# pcb-main.net
KiCad netlist of a schematic drawn in EAGLE
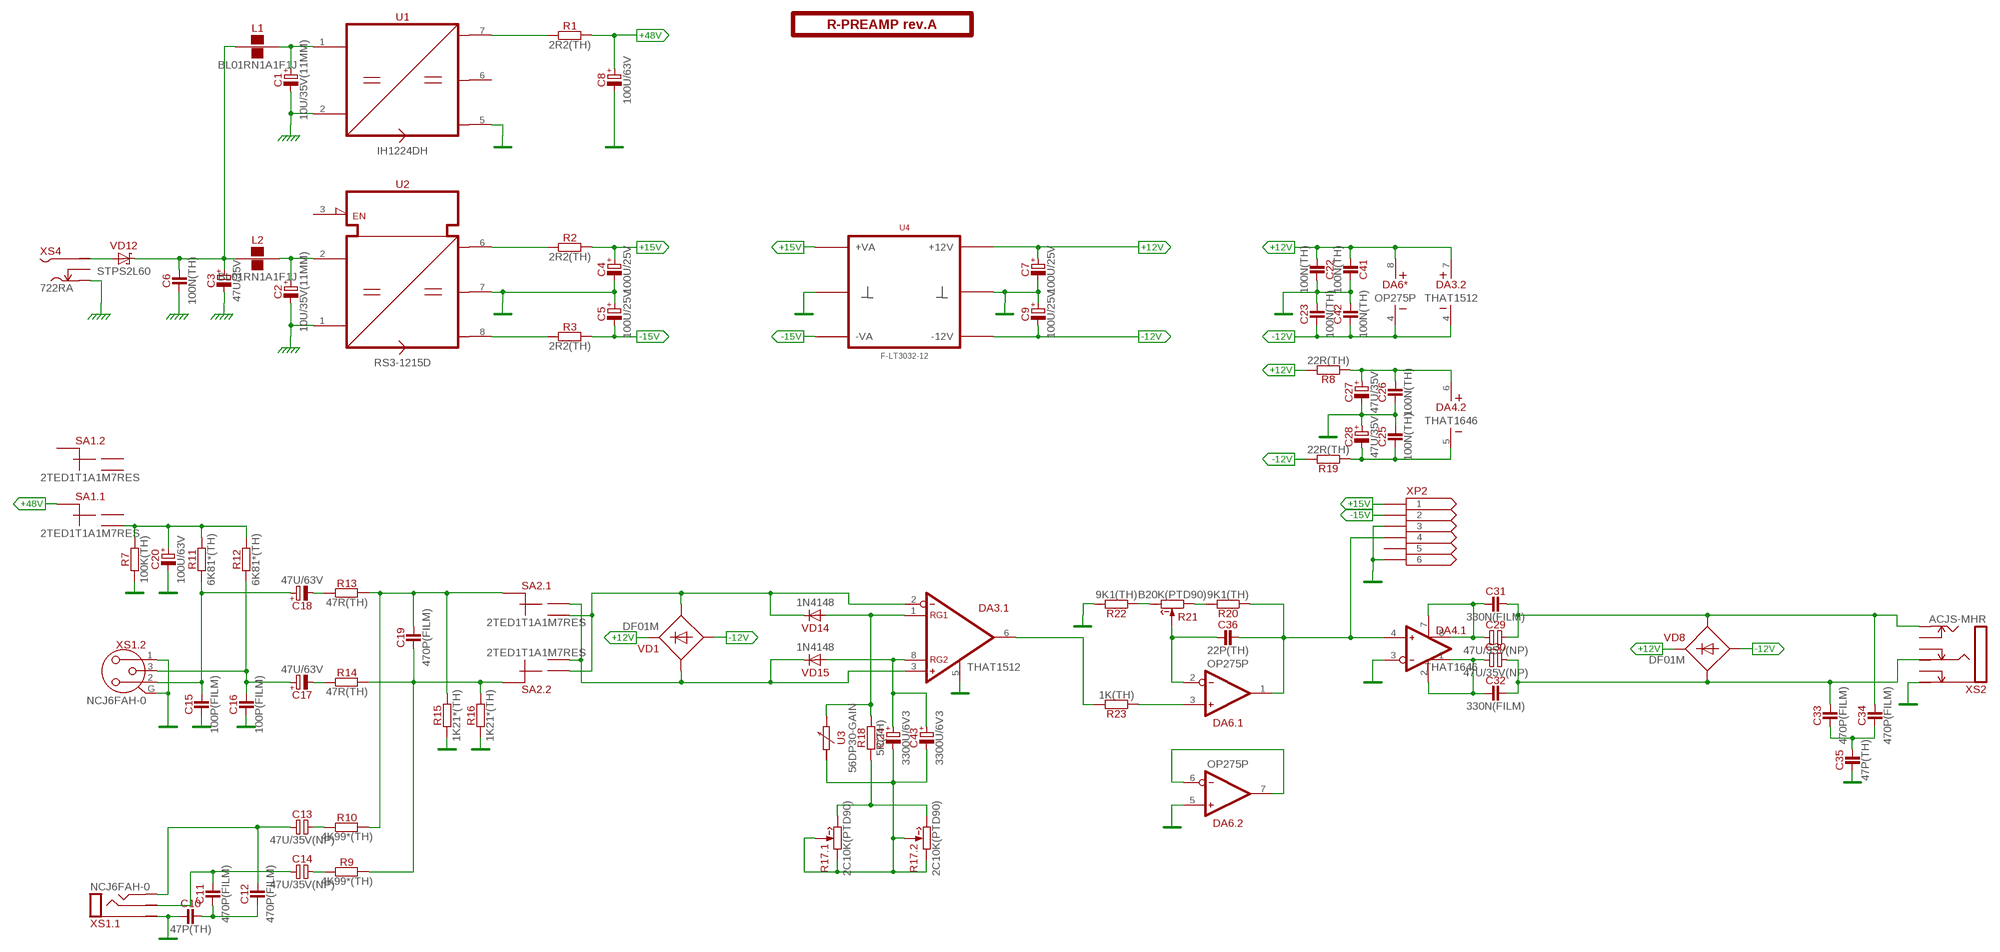
[diagram p0: schematic, sheet 1]

(export (version "E")
  (design (tool "Eeschema 10.0.6"))
  (components
    (comp (ref "C1")
      (value "10U/35V(11MM)")
      (footprint "eagle-import:E2-5")
      (libsource (lib "eagle-import") (part "?10U/35V(11MM)"))
    )
    (comp (ref "C2")
      (value "10U/35V(11MM)")
      (footprint "eagle-import:E2-5")
      (libsource (lib "eagle-import") (part "?10U/35V(11MM)"))
    )
    (comp (ref "C3")
      (value "47U/35V")
      (footprint "eagle-import:E2-5")
      (libsource (lib "eagle-import") (part "?47U/35V"))
    )
    (comp (ref "C4")
      (value "100U/25V")
      (footprint "eagle-import:E2,5-7")
      (libsource (lib "eagle-import") (part "?100U/25V"))
    )
    (comp (ref "C5")
      (value "100U/25V")
      (footprint "eagle-import:E2,5-7")
      (libsource (lib "eagle-import") (part "?100U/25V"))
    )
    (comp (ref "C6")
      (value "100N(TH)")
      (footprint "eagle-import:C050-024X044")
      (libsource (lib "eagle-import") (part "?100N(TH)"))
    )
    (comp (ref "C7")
      (value "100U/25V")
      (footprint "eagle-import:E2,5-7")
      (libsource (lib "eagle-import") (part "?100U/25V"))
    )
    (comp (ref "C8")
      (value "100U/63V")
      (footprint "eagle-import:E5-10,5")
      (libsource (lib "eagle-import") (part "?100U/63V"))
    )
    (comp (ref "C9")
      (value "100U/25V")
      (footprint "eagle-import:E2,5-7")
      (libsource (lib "eagle-import") (part "?100U/25V"))
    )
    (comp (ref "C10")
      (value "47P(TH)")
      (footprint "eagle-import:C050-024X044")
      (libsource (lib "eagle-import") (part "?47P(TH)"))
    )
    (comp (ref "C11")
      (value "470P(FILM)")
      (footprint "eagle-import:C050-055X075")
      (libsource (lib "eagle-import") (part "?470P(FILM)"))
    )
    (comp (ref "C12")
      (value "470P(FILM)")
      (footprint "eagle-import:C050-055X075")
      (libsource (lib "eagle-import") (part "?470P(FILM)"))
    )
    (comp (ref "C13")
      (value "47U/35V(NP)")
      (footprint "eagle-import:E5-10,5")
      (libsource (lib "eagle-import") (part "?(NP)47U/35V"))
    )
    (comp (ref "C14")
      (value "47U/35V(NP)")
      (footprint "eagle-import:E5-10,5")
      (libsource (lib "eagle-import") (part "?(NP)47U/35V"))
    )
    (comp (ref "C15")
      (value "100P(FILM)")
      (footprint "eagle-import:C050-045X075")
      (libsource (lib "eagle-import") (part "?100P(FILM)"))
    )
    (comp (ref "C16")
      (value "100P(FILM)")
      (footprint "eagle-import:C050-045X075")
      (libsource (lib "eagle-import") (part "?100P(FILM)"))
    )
    (comp (ref "C17")
      (value "47U/63V")
      (footprint "eagle-import:E5-10,5")
      (libsource (lib "eagle-import") (part "?47U/63V"))
    )
    (comp (ref "C18")
      (value "47U/63V")
      (footprint "eagle-import:E5-10,5")
      (libsource (lib "eagle-import") (part "?47U/63V"))
    )
    (comp (ref "C19")
      (value "470P(FILM)")
      (footprint "eagle-import:C050-055X075")
      (libsource (lib "eagle-import") (part "?470P(FILM)"))
    )
    (comp (ref "C20")
      (value "100U/63V")
      (footprint "eagle-import:E5-10,5")
      (libsource (lib "eagle-import") (part "?100U/63V"))
    )
    (comp (ref "C22")
      (value "100N(TH)")
      (footprint "eagle-import:C050-024X044")
      (libsource (lib "eagle-import") (part "?100N(TH)"))
    )
    (comp (ref "C23")
      (value "100N(TH)")
      (footprint "eagle-import:C050-024X044")
      (libsource (lib "eagle-import") (part "?100N(TH)"))
    )
    (comp (ref "C24")
      (value "3300U/6V3")
      (footprint "eagle-import:E5-10,5")
      (libsource (lib "eagle-import") (part "?3300U/6V3"))
    )
    (comp (ref "C25")
      (value "100N(TH)")
      (footprint "eagle-import:C050-024X044")
      (libsource (lib "eagle-import") (part "?100N(TH)"))
    )
    (comp (ref "C26")
      (value "100N(TH)")
      (footprint "eagle-import:C050-024X044")
      (libsource (lib "eagle-import") (part "?100N(TH)"))
    )
    (comp (ref "C27")
      (value "47U/35V")
      (footprint "eagle-import:E2-5")
      (libsource (lib "eagle-import") (part "?47U/35V"))
    )
    (comp (ref "C28")
      (value "47U/35V")
      (footprint "eagle-import:E2-5")
      (libsource (lib "eagle-import") (part "?47U/35V"))
    )
    (comp (ref "C29")
      (value "47U/35V(NP)")
      (footprint "eagle-import:E5-10,5")
      (libsource (lib "eagle-import") (part "?(NP)47U/35V"))
    )
    (comp (ref "C30")
      (value "47U/35V(NP)")
      (footprint "eagle-import:E5-10,5")
      (libsource (lib "eagle-import") (part "?(NP)47U/35V"))
    )
    (comp (ref "C31")
      (value "330N(FILM)")
      (footprint "eagle-import:C050-035X075")
      (libsource (lib "eagle-import") (part "?330N(FILM)"))
    )
    (comp (ref "C32")
      (value "330N(FILM)")
      (footprint "eagle-import:C050-035X075")
      (libsource (lib "eagle-import") (part "?330N(FILM)"))
    )
    (comp (ref "C33")
      (value "470P(FILM)")
      (footprint "eagle-import:C050-055X075")
      (libsource (lib "eagle-import") (part "?470P(FILM)"))
    )
    (comp (ref "C34")
      (value "470P(FILM)")
      (footprint "eagle-import:C050-055X075")
      (libsource (lib "eagle-import") (part "?470P(FILM)"))
    )
    (comp (ref "C35")
      (value "47P(TH)")
      (footprint "eagle-import:C050-024X044")
      (libsource (lib "eagle-import") (part "?47P(TH)"))
    )
    (comp (ref "C36")
      (value "22P(TH)")
      (footprint "eagle-import:C050-024X044")
      (libsource (lib "eagle-import") (part "?22P(TH)"))
    )
    (comp (ref "C41")
      (value "100N(TH)")
      (footprint "eagle-import:C050-024X044")
      (libsource (lib "eagle-import") (part "?100N(TH)"))
    )
    (comp (ref "C42")
      (value "100N(TH)")
      (footprint "eagle-import:C050-024X044")
      (libsource (lib "eagle-import") (part "?100N(TH)"))
    )
    (comp (ref "C43")
      (value "3300U/6V3")
      (footprint "eagle-import:E5-10,5")
      (libsource (lib "eagle-import") (part "?3300U/6V3"))
    )
    (comp (ref "DA3")
      (value "THAT1512")
      (footprint "eagle-import:DIP-8")
      (libsource (lib "eagle-import") (part "THAT1512"))
    )
    (comp (ref "DA4")
      (value "THAT1646")
      (footprint "eagle-import:DIP-8")
      (libsource (lib "eagle-import") (part "THAT1646"))
    )
    (comp (ref "DA6")
      (value "OP275P")
      (footprint "eagle-import:DIP-8")
      (libsource (lib "eagle-import") (part "OP275P"))
    )
    (comp (ref "L1")
      (value "BL01RN1A1F1J")
      (footprint "eagle-import:BL01RN1A")
      (libsource (lib "eagle-import") (part "BL01RN1A?1F1J"))
    )
    (comp (ref "L2")
      (value "BL01RN1A1F1J")
      (footprint "eagle-import:BL01RN1A")
      (libsource (lib "eagle-import") (part "BL01RN1A?1F1J"))
    )
    (comp (ref "PCB1")
      (value "R-PREAMP rev.A")
      (footprint "eagle-import:F-LOGO")
      (libsource (lib "eagle-import") (part "GENERIC-LOGO"))
    )
    (comp (ref "R1")
      (value "2R2(TH)")
      (footprint "eagle-import:R-0207_10")
      (libsource (lib "eagle-import") (part "?2R2(TH)"))
    )
    (comp (ref "R2")
      (value "2R2(TH)")
      (footprint "eagle-import:R-0207_10")
      (libsource (lib "eagle-import") (part "?2R2(TH)"))
    )
    (comp (ref "R3")
      (value "2R2(TH)")
      (footprint "eagle-import:R-0207_10")
      (libsource (lib "eagle-import") (part "?2R2(TH)"))
    )
    (comp (ref "R7")
      (value "100K(TH)")
      (footprint "eagle-import:R-0207_10")
      (libsource (lib "eagle-import") (part "resistors_?100K(TH)"))
    )
    (comp (ref "R8")
      (value "22R(TH)")
      (footprint "eagle-import:R-0207_10")
      (libsource (lib "eagle-import") (part "?22R(TH)"))
    )
    (comp (ref "R9")
      (value "4K99*(TH)")
      (footprint "eagle-import:R-0207_10")
      (libsource (lib "eagle-import") (part "?4K99(TH)"))
    )
    (comp (ref "R10")
      (value "4K99*(TH)")
      (footprint "eagle-import:R-0207_10")
      (libsource (lib "eagle-import") (part "?4K99(TH)"))
    )
    (comp (ref "R11")
      (value "6K81*(TH)")
      (footprint "eagle-import:R-0207_10")
      (libsource (lib "eagle-import") (part "?6K81(TH)"))
    )
    (comp (ref "R12")
      (value "6K81*(TH)")
      (footprint "eagle-import:R-0207_10")
      (libsource (lib "eagle-import") (part "?6K81(TH)"))
    )
    (comp (ref "R13")
      (value "47R(TH)")
      (footprint "eagle-import:R-0207_10")
      (libsource (lib "eagle-import") (part "?47R(TH)"))
    )
    (comp (ref "R14")
      (value "47R(TH)")
      (footprint "eagle-import:R-0207_10")
      (libsource (lib "eagle-import") (part "?47R(TH)"))
    )
    (comp (ref "R15")
      (value "1K21*(TH)")
      (footprint "eagle-import:R-0207_10")
      (libsource (lib "eagle-import") (part "?1K21(TH)"))
    )
    (comp (ref "R16")
      (value "1K21*(TH)")
      (footprint "eagle-import:R-0207_10")
      (libsource (lib "eagle-import") (part "?1K21(TH)"))
    )
    (comp (ref "R17")
      (value "2C10K(PTD90)")
      (footprint "eagle-import:PTD902")
      (libsource (lib "eagle-import") (part "2?(PTD90)C10K"))
    )
    (comp (ref "R18")
      (value "5R(TH)")
      (footprint "eagle-import:R-0207_10")
      (libsource (lib "eagle-import") (part "?5R(TH)"))
    )
    (comp (ref "R19")
      (value "22R(TH)")
      (footprint "eagle-import:R-0207_10")
      (libsource (lib "eagle-import") (part "?22R(TH)"))
    )
    (comp (ref "R20")
      (value "9K1(TH)")
      (footprint "eagle-import:R-0207_10")
      (libsource (lib "eagle-import") (part "?9K1(TH)"))
    )
    (comp (ref "R21")
      (value "B20K(PTD90)")
      (footprint "eagle-import:PTD901")
      (libsource (lib "eagle-import") (part "?(PTD90)B20K"))
    )
    (comp (ref "R22")
      (value "9K1(TH)")
      (footprint "eagle-import:R-0207_10")
      (libsource (lib "eagle-import") (part "?9K1(TH)"))
    )
    (comp (ref "R23")
      (value "1K(TH)")
      (footprint "eagle-import:R-0207_10")
      (libsource (lib "eagle-import") (part "?1K(TH)"))
    )
    (comp (ref "SA1")
      (value "2TED1T1A1M7RES")
      (footprint "eagle-import:2TED1T1A1M7RES")
      (libsource (lib "eagle-import") (part "2TED1T1A1M7RES"))
    )
    (comp (ref "SA2")
      (value "2TED1T1A1M7RES")
      (footprint "eagle-import:2TED1T1A1M7RES")
      (libsource (lib "eagle-import") (part "2TED1T1A1M7RES"))
    )
    (comp (ref "U1")
      (value "IH1224DH")
      (footprint "eagle-import:SIP7")
      (libsource (lib "eagle-import") (part "IH1224DH"))
    )
    (comp (ref "U2")
      (value "RS3-1215D")
      (footprint "eagle-import:SIP8")
      (libsource (lib "eagle-import") (part "RS3-1215D"))
    )
    (comp (ref "U3")
      (value "56DP30-GAIN")
      (footprint "eagle-import:F56DP")
      (libsource (lib "eagle-import") (part "F56DP"))
    )
    (comp (ref "U4")
      (value "F-LT3032-12")
      (footprint "eagle-import:F-DIP8-HEATSINK")
      (libsource (lib "eagle-import") (part "F-DUAL-SUPPLY"))
    )
    (comp (ref "VD1")
      (value "DF01M")
      (footprint "eagle-import:MDIP-4")
      (libsource (lib "eagle-import") (part "DF?M01"))
    )
    (comp (ref "VD8")
      (value "DF01M")
      (footprint "eagle-import:MDIP-4")
      (libsource (lib "eagle-import") (part "DF?M01"))
    )
    (comp (ref "VD12")
      (value "STPS2L60")
      (footprint "eagle-import:DO41-10")
      (libsource (lib "eagle-import") (part "?STPS2L60"))
    )
    (comp (ref "VD14")
      (value "1N4148")
      (footprint "eagle-import:DO35-7")
      (libsource (lib "eagle-import") (part "?1N4148"))
    )
    (comp (ref "VD15")
      (value "1N4148")
      (footprint "eagle-import:DO35-7")
      (libsource (lib "eagle-import") (part "?1N4148"))
    )
    (comp (ref "XP2")
      (value "CONN-6-NORMAL")
      (footprint "eagle-import:MA03-2")
      (libsource (lib "eagle-import") (part "CONN-6-?NORMAL"))
    )
    (comp (ref "XS1")
      (value "NCJ6FAH-0")
      (footprint "eagle-import:NCJ6FA-H-0")
      (libsource (lib "eagle-import") (part "NCJ6FAH-0"))
    )
    (comp (ref "XS2")
      (value "ACJS-MHR")
      (footprint "eagle-import:NMJ6HC-S")
      (libsource (lib "eagle-import") (part "ACJS-MHR"))
    )
    (comp (ref "XS4")
      (value "722RA")
      (footprint "eagle-import:SWITCHCRAFT-L712RA")
      (libsource (lib "eagle-import") (part "722RA"))
    )
  )
  (nets
    (net (code "1") (name "+12V") (class "Default")
      (node (ref "C22") (pin "2") (pinfunction "2_2") (pintype "passive"))
      (node (ref "C41") (pin "2") (pinfunction "2_2") (pintype "passive"))
      (node (ref "C7") (pin "+") (pinfunction "+_+") (pintype "passive"))
      (node (ref "DA3") (pin "7") (pinfunction "V+_7") (pintype "power_in"))
      (node (ref "DA6") (pin "8") (pinfunction "V+_8") (pintype "power_in"))
      (node (ref "R8") (pin "2") (pinfunction "2_2") (pintype "passive"))
      (node (ref "U4") (pin "8") (pinfunction "P+12V_8") (pintype "bidirectional"))
      (node (ref "VD1") (pin "3") (pinfunction "C_3") (pintype "passive"))
      (node (ref "VD8") (pin "3") (pinfunction "C_3") (pintype "passive"))
    )
    (net (code "2") (name "+15V") (class "Default")
      (node (ref "C4") (pin "+") (pinfunction "+_+") (pintype "passive"))
      (node (ref "R2") (pin "2") (pinfunction "2_2") (pintype "passive"))
      (node (ref "U4") (pin "1") (pinfunction "P+VA_1") (pintype "bidirectional"))
      (node (ref "XP2") (pin "1") (pinfunction "1_1") (pintype "passive"))
    )
    (net (code "3") (name "+48V") (class "Default")
      (node (ref "C8") (pin "+") (pinfunction "+_+") (pintype "passive"))
      (node (ref "R1") (pin "2") (pinfunction "2_2") (pintype "passive"))
      (node (ref "SA1") (pin "C1") (pinfunction "CM_C1") (pintype "passive"))
    )
    (net (code "4") (name "-12V") (class "Default")
      (node (ref "C23") (pin "2") (pinfunction "2_2") (pintype "passive"))
      (node (ref "C42") (pin "2") (pinfunction "2_2") (pintype "passive"))
      (node (ref "C9") (pin "-") (pinfunction "-_-") (pintype "passive"))
      (node (ref "DA3") (pin "4") (pinfunction "V-_4") (pintype "power_in"))
      (node (ref "DA6") (pin "4") (pinfunction "V-_4") (pintype "power_in"))
      (node (ref "R19") (pin "2") (pinfunction "2_2") (pintype "passive"))
      (node (ref "U4") (pin "5") (pinfunction "P-12V_5") (pintype "bidirectional"))
      (node (ref "VD1") (pin "4") (pinfunction "A_4") (pintype "passive"))
      (node (ref "VD8") (pin "4") (pinfunction "A_4") (pintype "passive"))
    )
    (net (code "5") (name "-15V") (class "Default")
      (node (ref "C5") (pin "-") (pinfunction "-_-") (pintype "passive"))
      (node (ref "R3") (pin "2") (pinfunction "2_2") (pintype "passive"))
      (node (ref "U4") (pin "4") (pinfunction "P-VA_4") (pintype "bidirectional"))
      (node (ref "XP2") (pin "2") (pinfunction "2_2") (pintype "passive"))
    )
    (net (code "6") (name "CHASSIS") (class "Default")
      (node (ref "C1") (pin "-") (pinfunction "-_-") (pintype "passive"))
      (node (ref "C2") (pin "-") (pinfunction "-_-") (pintype "passive"))
      (node (ref "C3") (pin "-") (pinfunction "-_-") (pintype "passive"))
      (node (ref "C6") (pin "1") (pinfunction "1_1") (pintype "passive"))
      (node (ref "U1") (pin "2") (pinfunction "IN-_2") (pintype "power_in"))
      (node (ref "U2") (pin "1") (pinfunction "IN-_1") (pintype "power_in"))
      (node (ref "XS4") (pin "S") (pinfunction "S_S") (pintype "passive"))
    )
    (net (code "7") (name "GND") (class "Default")
      (node (ref "C10") (pin "1") (pinfunction "1_1") (pintype "passive"))
      (node (ref "C15") (pin "1") (pinfunction "1_1") (pintype "passive"))
      (node (ref "C16") (pin "1") (pinfunction "1_1") (pintype "passive"))
      (node (ref "C20") (pin "-") (pinfunction "-_-") (pintype "passive"))
      (node (ref "C22") (pin "1") (pinfunction "1_1") (pintype "passive"))
      (node (ref "C23") (pin "1") (pinfunction "1_1") (pintype "passive"))
      (node (ref "C25") (pin "1") (pinfunction "1_1") (pintype "passive"))
      (node (ref "C26") (pin "2") (pinfunction "2_2") (pintype "passive"))
      (node (ref "C27") (pin "-") (pinfunction "-_-") (pintype "passive"))
      (node (ref "C28") (pin "+") (pinfunction "+_+") (pintype "passive"))
      (node (ref "C35") (pin "1") (pinfunction "1_1") (pintype "passive"))
      (node (ref "C4") (pin "-") (pinfunction "-_-") (pintype "passive"))
      (node (ref "C41") (pin "1") (pinfunction "1_1") (pintype "passive"))
      (node (ref "C42") (pin "1") (pinfunction "1_1") (pintype "passive"))
      (node (ref "C5") (pin "+") (pinfunction "+_+") (pintype "passive"))
      (node (ref "C7") (pin "-") (pinfunction "-_-") (pintype "passive"))
      (node (ref "C8") (pin "-") (pinfunction "-_-") (pintype "passive"))
      (node (ref "C9") (pin "+") (pinfunction "+_+") (pintype "passive"))
      (node (ref "DA3") (pin "5") (pinfunction "REF_5") (pintype "output"))
      (node (ref "DA4") (pin "3") (pinfunction "IN-_3") (pintype "input"))
      (node (ref "DA6") (pin "5") (pinfunction "IN+_5") (pintype "input"))
      (node (ref "R15") (pin "1") (pinfunction "1_1") (pintype "passive"))
      (node (ref "R16") (pin "1") (pinfunction "1_1") (pintype "passive"))
      (node (ref "R22") (pin "2") (pinfunction "2_2") (pintype "passive"))
      (node (ref "R7") (pin "1") (pinfunction "1_1") (pintype "passive"))
      (node (ref "U1") (pin "5") (pinfunction "V-_5") (pintype "passive"))
      (node (ref "U2") (pin "7") (pinfunction "GND_7") (pintype "passive"))
      (node (ref "U4") (pin "2") (pinfunction "GND1_2") (pintype "bidirectional"))
      (node (ref "U4") (pin "3") (pinfunction "GND1_3") (pintype "bidirectional"))
      (node (ref "U4") (pin "6") (pinfunction "GND_6") (pintype "bidirectional"))
      (node (ref "U4") (pin "7") (pinfunction "GND_7") (pintype "bidirectional"))
      (node (ref "XP2") (pin "3") (pinfunction "3_3") (pintype "passive"))
      (node (ref "XP2") (pin "6") (pinfunction "6_6") (pintype "passive"))
      (node (ref "XS1") (pin "1") (pinfunction "1_1") (pintype "passive"))
      (node (ref "XS1") (pin "G") (pinfunction "G_G") (pintype "passive"))
      (node (ref "XS1") (pin "S") (pinfunction "S_S") (pintype "passive"))
      (node (ref "XS2") (pin "S") (pinfunction "S_S") (pintype "passive"))
    )
    (net (code "8") (name "Net-(C3-Pad+)") (class "Default")
      (node (ref "C3") (pin "+") (pinfunction "+_+") (pintype "passive"))
      (node (ref "C6") (pin "2") (pinfunction "2_2") (pintype "passive"))
      (node (ref "L1") (pin "1") (pinfunction "1_1") (pintype "passive"))
      (node (ref "L2") (pin "1") (pinfunction "1_1") (pintype "passive"))
      (node (ref "VD12") (pin "C") (pinfunction "C_C") (pintype "passive"))
    )
    (net (code "9") (name "Net-(C10-Pad2)") (class "Default")
      (node (ref "C10") (pin "2") (pinfunction "2_2") (pintype "passive"))
      (node (ref "C11") (pin "1") (pinfunction "1_1") (pintype "passive"))
      (node (ref "C12") (pin "1") (pinfunction "1_1") (pintype "passive"))
    )
    (net (code "10") (name "Net-(C11-Pad2)") (class "Default")
      (node (ref "C11") (pin "2") (pinfunction "2_2") (pintype "passive"))
      (node (ref "C14") (pin "+") (pinfunction "+_+") (pintype "passive"))
      (node (ref "XS1") (pin "R") (pinfunction "R_R") (pintype "passive"))
    )
    (net (code "11") (name "Net-(C12-Pad2)") (class "Default")
      (node (ref "C12") (pin "2") (pinfunction "2_2") (pintype "passive"))
      (node (ref "C13") (pin "+") (pinfunction "+_+") (pintype "passive"))
      (node (ref "XS1") (pin "T1") (pinfunction "T_T1") (pintype "passive"))
      (node (ref "XS1") (pin "T2") (pinfunction "T_T2") (pintype "passive"))
    )
    (net (code "12") (name "Net-(C13-Pad-)") (class "Default")
      (node (ref "C13") (pin "-") (pinfunction "-_-") (pintype "passive"))
      (node (ref "R10") (pin "1") (pinfunction "1_1") (pintype "passive"))
    )
    (net (code "13") (name "Net-(C14-Pad-)") (class "Default")
      (node (ref "C14") (pin "-") (pinfunction "-_-") (pintype "passive"))
      (node (ref "R9") (pin "1") (pinfunction "1_1") (pintype "passive"))
    )
    (net (code "14") (name "Net-(C15-Pad2)") (class "Default")
      (node (ref "C15") (pin "2") (pinfunction "2_2") (pintype "passive"))
      (node (ref "C18") (pin "+") (pinfunction "+_+") (pintype "passive"))
      (node (ref "R11") (pin "1") (pinfunction "1_1") (pintype "passive"))
      (node (ref "XS1") (pin "2") (pinfunction "2_2") (pintype "passive"))
    )
    (net (code "15") (name "Net-(C16-Pad2)") (class "Default")
      (node (ref "C16") (pin "2") (pinfunction "2_2") (pintype "passive"))
      (node (ref "C17") (pin "+") (pinfunction "+_+") (pintype "passive"))
      (node (ref "R12") (pin "1") (pinfunction "1_1") (pintype "passive"))
      (node (ref "XS1") (pin "3") (pinfunction "3_3") (pintype "passive"))
    )
    (net (code "16") (name "Net-(C17-Pad-)") (class "Default")
      (node (ref "C17") (pin "-") (pinfunction "-_-") (pintype "passive"))
      (node (ref "R14") (pin "1") (pinfunction "1_1") (pintype "passive"))
    )
    (net (code "17") (name "Net-(C18-Pad-)") (class "Default")
      (node (ref "C18") (pin "-") (pinfunction "-_-") (pintype "passive"))
      (node (ref "R13") (pin "1") (pinfunction "1_1") (pintype "passive"))
    )
    (net (code "18") (name "Net-(C33-Pad1)") (class "Default")
      (node (ref "C33") (pin "1") (pinfunction "1_1") (pintype "passive"))
      (node (ref "C34") (pin "1") (pinfunction "1_1") (pintype "passive"))
      (node (ref "C35") (pin "2") (pinfunction "2_2") (pintype "passive"))
    )
    (net (code "19") (name "Net-(DA3A-IN+)") (class "Default")
      (node (ref "DA3") (pin "3") (pinfunction "IN+_3") (pintype "input"))
      (node (ref "SA2") (pin "NC1") (pinfunction "1_NC1") (pintype "passive"))
      (node (ref "SA2") (pin "NO2") (pinfunction "2_NO2") (pintype "passive"))
      (node (ref "VD1") (pin "1") (pinfunction "AC1_1") (pintype "passive"))
      (node (ref "VD15") (pin "C") (pinfunction "C_C") (pintype "passive"))
    )
    (net (code "20") (name "Net-(DA3A-IN-)") (class "Default")
      (node (ref "DA3") (pin "2") (pinfunction "IN-_2") (pintype "input"))
      (node (ref "SA2") (pin "NC2") (pinfunction "1_NC2") (pintype "passive"))
      (node (ref "SA2") (pin "NO1") (pinfunction "2_NO1") (pintype "passive"))
      (node (ref "VD1") (pin "2") (pinfunction "AC2_2") (pintype "passive"))
      (node (ref "VD14") (pin "C") (pinfunction "C_C") (pintype "passive"))
    )
    (net (code "21") (name "Net-(DA3A-OUT)") (class "Default")
      (node (ref "DA3") (pin "6") (pinfunction "OUT_6") (pintype "output"))
      (node (ref "R23") (pin "2") (pinfunction "2_2") (pintype "passive"))
    )
    (net (code "22") (name "Net-(DA3A-RG1)") (class "Default")
      (node (ref "DA3") (pin "1") (pinfunction "RG1_1") (pintype "input"))
      (node (ref "R18") (pin "2") (pinfunction "2_2") (pintype "passive"))
      (node (ref "U3") (pin "3") (pinfunction "E_3") (pintype "passive"))
      (node (ref "U3") (pin "4") (pinfunction "E_4") (pintype "passive"))
      (node (ref "VD14") (pin "A") (pinfunction "A_A") (pintype "passive"))
    )
    (net (code "23") (name "Net-(DA3A-RG2)") (class "Default")
      (node (ref "C24") (pin "+") (pinfunction "+_+") (pintype "passive"))
      (node (ref "C43") (pin "+") (pinfunction "+_+") (pintype "passive"))
      (node (ref "DA3") (pin "8") (pinfunction "RG2_8") (pintype "input"))
      (node (ref "VD15") (pin "A") (pinfunction "A_A") (pintype "passive"))
    )
    (net (code "24") (name "Net-(DA4A-IN+)") (class "Default")
      (node (ref "C36") (pin "2") (pinfunction "2_2") (pintype "passive"))
      (node (ref "DA4") (pin "4") (pinfunction "IN+_4") (pintype "input"))
      (node (ref "DA6") (pin "1") (pinfunction "OUT_1") (pintype "output"))
      (node (ref "R20") (pin "1") (pinfunction "1_1") (pintype "passive"))
      (node (ref "XP2") (pin "4") (pinfunction "4_4") (pintype "passive"))
    )
    (net (code "25") (name "Net-(DA4A-OUT+)") (class "Default")
      (node (ref "C29") (pin "+") (pinfunction "+_+") (pintype "passive"))
      (node (ref "C31") (pin "1") (pinfunction "1_1") (pintype "passive"))
      (node (ref "DA4") (pin "7") (pinfunction "SENS+_7") (pintype "input"))
      (node (ref "DA4") (pin "8") (pinfunction "OUT+_8") (pintype "output"))
    )
    (net (code "26") (name "Net-(DA4A-OUT-)") (class "Default")
      (node (ref "C30") (pin "+") (pinfunction "+_+") (pintype "passive"))
      (node (ref "C32") (pin "1") (pinfunction "1_1") (pintype "passive"))
      (node (ref "DA4") (pin "1") (pinfunction "OUT-_1") (pintype "output"))
      (node (ref "DA4") (pin "2") (pinfunction "SENS-_2") (pintype "input"))
    )
    (net (code "27") (name "Net-(DA4B-V+)") (class "Default")
      (node (ref "C26") (pin "1") (pinfunction "1_1") (pintype "passive"))
      (node (ref "C27") (pin "+") (pinfunction "+_+") (pintype "passive"))
      (node (ref "DA4") (pin "6") (pinfunction "V+_6") (pintype "power_in"))
      (node (ref "R8") (pin "1") (pinfunction "1_1") (pintype "passive"))
    )
    (net (code "28") (name "Net-(DA4B-V-)") (class "Default")
      (node (ref "C25") (pin "2") (pinfunction "2_2") (pintype "passive"))
      (node (ref "C28") (pin "-") (pinfunction "-_-") (pintype "passive"))
      (node (ref "DA4") (pin "5") (pinfunction "V-_5") (pintype "power_in"))
      (node (ref "R19") (pin "1") (pinfunction "1_1") (pintype "passive"))
    )
    (net (code "29") (name "Net-(DA6B-IN+)") (class "Default")
      (node (ref "DA6") (pin "3") (pinfunction "IN+_3") (pintype "input"))
      (node (ref "R23") (pin "1") (pinfunction "1_1") (pintype "passive"))
    )
    (net (code "30") (name "Net-(DA6B-IN-)") (class "Default")
      (node (ref "C36") (pin "1") (pinfunction "1_1") (pintype "passive"))
      (node (ref "DA6") (pin "2") (pinfunction "IN-_2") (pintype "input"))
      (node (ref "R21") (pin "2") (pinfunction "W_2") (pintype "passive"))
    )
    (net (code "31") (name "Net-(DA6C-IN-)") (class "Default")
      (node (ref "DA6") (pin "6") (pinfunction "IN-_6") (pintype "input"))
      (node (ref "DA6") (pin "7") (pinfunction "OUT_7") (pintype "output"))
    )
    (net (code "32") (name "Net-(R17A-CCW)") (class "Default")
      (node (ref "C24") (pin "-") (pinfunction "-_-") (pintype "passive"))
      (node (ref "C43") (pin "-") (pinfunction "-_-") (pintype "passive"))
      (node (ref "R17") (pin "A1") (pinfunction "CCW_A1") (pintype "passive"))
      (node (ref "R17") (pin "A2") (pinfunction "W_A2") (pintype "passive"))
      (node (ref "R17") (pin "B1") (pinfunction "CCW_B1") (pintype "passive"))
      (node (ref "R17") (pin "B2") (pinfunction "W_B2") (pintype "passive"))
      (node (ref "U3") (pin "1") (pinfunction "A_1") (pintype "passive"))
      (node (ref "U3") (pin "2") (pinfunction "A_2") (pintype "passive"))
    )
    (net (code "33") (name "Net-(R17A-CW)") (class "Default")
      (node (ref "R17") (pin "A3") (pinfunction "CW_A3") (pintype "passive"))
      (node (ref "R17") (pin "B3") (pinfunction "CW_B3") (pintype "passive"))
      (node (ref "R18") (pin "1") (pinfunction "1_1") (pintype "passive"))
    )
    (net (code "34") (name "Net-(R21-CCW)") (class "Default")
      (node (ref "R20") (pin "2") (pinfunction "2_2") (pintype "passive"))
      (node (ref "R21") (pin "1") (pinfunction "CCW_1") (pintype "passive"))
    )
    (net (code "35") (name "Net-(R21-CW)") (class "Default")
      (node (ref "R21") (pin "3") (pinfunction "CW_3") (pintype "passive"))
      (node (ref "R22") (pin "1") (pinfunction "1_1") (pintype "passive"))
    )
    (net (code "36") (name "Net-(SA1A-2)") (class "Default")
      (node (ref "C20") (pin "+") (pinfunction "+_+") (pintype "passive"))
      (node (ref "R11") (pin "2") (pinfunction "2_2") (pintype "passive"))
      (node (ref "R12") (pin "2") (pinfunction "2_2") (pintype "passive"))
      (node (ref "R7") (pin "2") (pinfunction "2_2") (pintype "passive"))
      (node (ref "SA1") (pin "NO1") (pinfunction "2_NO1") (pintype "passive"))
    )
    (net (code "37") (name "Net-(SA2A-CM)") (class "Default")
      (node (ref "C19") (pin "2") (pinfunction "2_2") (pintype "passive"))
      (node (ref "R10") (pin "2") (pinfunction "2_2") (pintype "passive"))
      (node (ref "R13") (pin "2") (pinfunction "2_2") (pintype "passive"))
      (node (ref "R15") (pin "2") (pinfunction "2_2") (pintype "passive"))
      (node (ref "SA2") (pin "C1") (pinfunction "CM_C1") (pintype "passive"))
    )
    (net (code "38") (name "Net-(SA2B-CM)") (class "Default")
      (node (ref "C19") (pin "1") (pinfunction "1_1") (pintype "passive"))
      (node (ref "R14") (pin "2") (pinfunction "2_2") (pintype "passive"))
      (node (ref "R16") (pin "2") (pinfunction "2_2") (pintype "passive"))
      (node (ref "R9") (pin "2") (pinfunction "2_2") (pintype "passive"))
      (node (ref "SA2") (pin "C2") (pinfunction "CM_C2") (pintype "passive"))
    )
    (net (code "39") (name "Net-(U1-IN+)") (class "Default")
      (node (ref "C1") (pin "+") (pinfunction "+_+") (pintype "passive"))
      (node (ref "L1") (pin "2") (pinfunction "2_2") (pintype "passive"))
      (node (ref "U1") (pin "1") (pinfunction "IN+_1") (pintype "power_in"))
    )
    (net (code "40") (name "Net-(U1-V+)") (class "Default")
      (node (ref "R1") (pin "1") (pinfunction "1_1") (pintype "passive"))
      (node (ref "U1") (pin "7") (pinfunction "V+_7") (pintype "passive"))
    )
    (net (code "41") (name "Net-(U2-IN+)") (class "Default")
      (node (ref "C2") (pin "+") (pinfunction "+_+") (pintype "passive"))
      (node (ref "L2") (pin "2") (pinfunction "2_2") (pintype "passive"))
      (node (ref "U2") (pin "2") (pinfunction "IN+_2") (pintype "power_in"))
    )
    (net (code "42") (name "Net-(U2-V+)") (class "Default")
      (node (ref "R2") (pin "1") (pinfunction "1_1") (pintype "passive"))
      (node (ref "U2") (pin "6") (pinfunction "V+_6") (pintype "passive"))
    )
    (net (code "43") (name "Net-(U2-V-)") (class "Default")
      (node (ref "R3") (pin "1") (pinfunction "1_1") (pintype "passive"))
      (node (ref "U2") (pin "8") (pinfunction "V-_8") (pintype "passive"))
    )
    (net (code "44") (name "Net-(VD8-AC1)") (class "Default")
      (node (ref "C29") (pin "-") (pinfunction "-_-") (pintype "passive"))
      (node (ref "C31") (pin "2") (pinfunction "2_2") (pintype "passive"))
      (node (ref "C34") (pin "2") (pinfunction "2_2") (pintype "passive"))
      (node (ref "VD8") (pin "1") (pinfunction "AC1_1") (pintype "passive"))
      (node (ref "XS2") (pin "T") (pinfunction "T_T") (pintype "passive"))
    )
    (net (code "45") (name "Net-(VD8-AC2)") (class "Default")
      (node (ref "C30") (pin "-") (pinfunction "-_-") (pintype "passive"))
      (node (ref "C32") (pin "2") (pinfunction "2_2") (pintype "passive"))
      (node (ref "C33") (pin "2") (pinfunction "2_2") (pintype "passive"))
      (node (ref "VD8") (pin "2") (pinfunction "AC2_2") (pintype "passive"))
      (node (ref "XS2") (pin "R") (pinfunction "R_R") (pintype "passive"))
    )
    (net (code "46") (name "Net-(VD12-PadA)") (class "Default")
      (node (ref "VD12") (pin "A") (pinfunction "A_A") (pintype "passive"))
      (node (ref "XS4") (pin "P") (pinfunction "P_P") (pintype "passive"))
    )
    (net (code "47") (name "unconnected-(SA1A-1-PadNC1)") (class "Default")
      (node (ref "SA1") (pin "NC1") (pinfunction "1_NC1") (pintype "passive"))
    )
    (net (code "48") (name "unconnected-(SA1B-1-PadNC2)") (class "Default")
      (node (ref "SA1") (pin "NC2") (pinfunction "1_NC2") (pintype "passive"))
    )
    (net (code "49") (name "unconnected-(SA1B-2-PadNO2)") (class "Default")
      (node (ref "SA1") (pin "NO2") (pinfunction "2_NO2") (pintype "passive"))
    )
    (net (code "50") (name "unconnected-(SA1B-CM-PadC2)") (class "Default")
      (node (ref "SA1") (pin "C2") (pinfunction "CM_C2") (pintype "passive"))
    )
    (net (code "51") (name "unconnected-(U1-GND-Pad6)") (class "Default")
      (node (ref "U1") (pin "6") (pinfunction "GND_6") (pintype "passive"))
    )
    (net (code "52") (name "unconnected-(U2-EN-Pad3)") (class "Default")
      (node (ref "U2") (pin "3") (pinfunction "EN_3") (pintype "bidirectional"))
    )
    (net (code "53") (name "unconnected-(XP2-Pad5)") (class "Default")
      (node (ref "XP2") (pin "5") (pinfunction "5_5") (pintype "passive"))
    )
    (net (code "54") (name "unconnected-(XS2-PadRN)") (class "Default")
      (node (ref "XS2") (pin "RN") (pinfunction "RN_RN") (pintype "passive"))
    )
    (net (code "55") (name "unconnected-(XS2-PadSN)") (class "Default")
      (node (ref "XS2") (pin "SN") (pinfunction "SN_SN") (pintype "passive"))
    )
    (net (code "56") (name "unconnected-(XS2-PadTN)") (class "Default")
      (node (ref "XS2") (pin "TN") (pinfunction "TN_TN") (pintype "passive"))
    )
    (net (code "57") (name "unconnected-(XS4-PadSS)") (class "Default")
      (node (ref "XS4") (pin "SS") (pinfunction "SS_SS") (pintype "passive"))
    )
  )
)
